# TSL2561_5V_REV-A.net
KiCad netlist of a schematic drawn in EAGLE
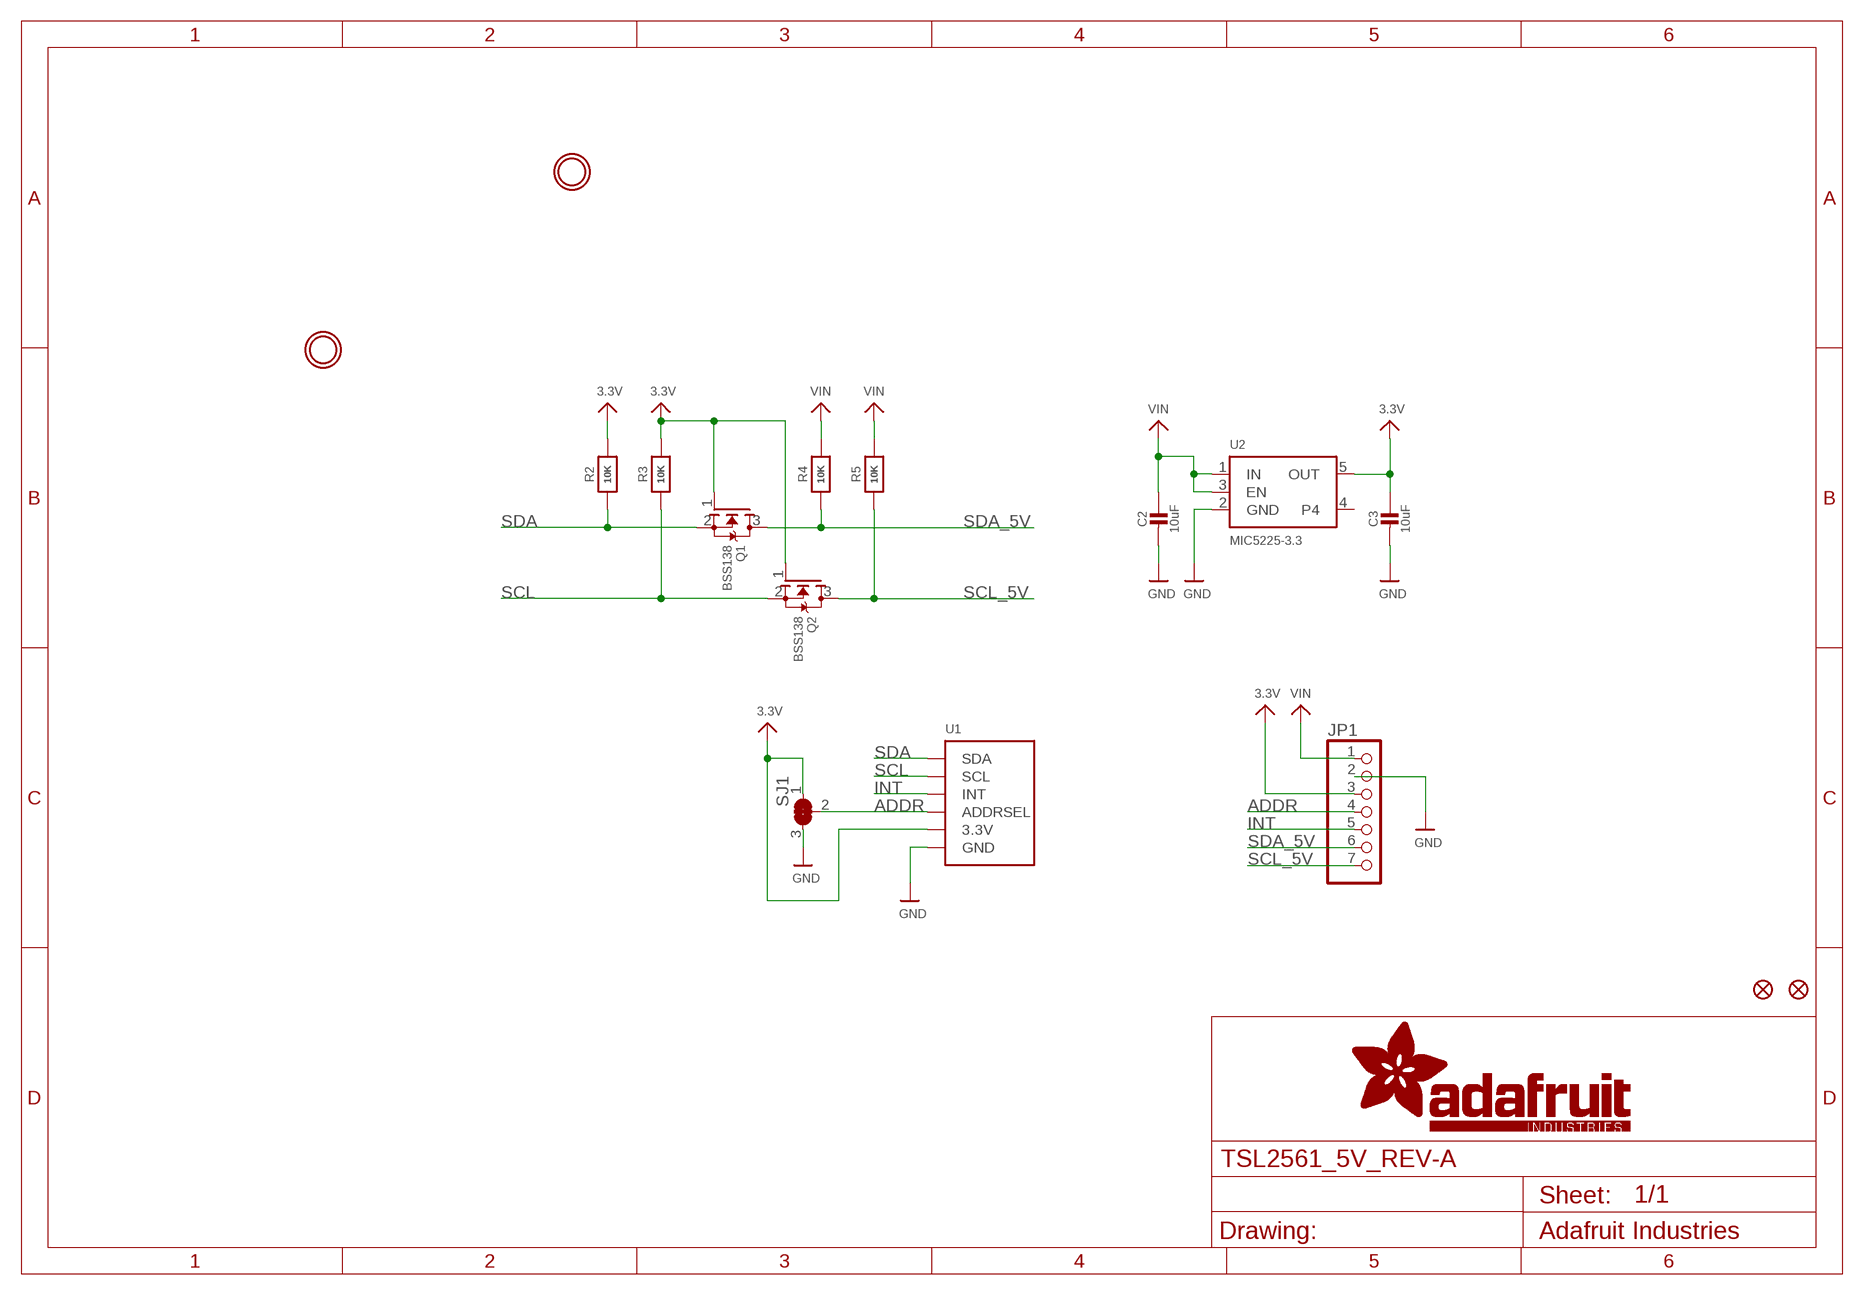
[diagram p0: schematic, sheet 1]

(export (version "E")
  (design (tool "Eeschema 10.0.6"))
  (components
    (comp (ref "C2")
      (value "10uF")
      (footprint "eagle-import:0805-NO")
      (libsource (lib "eagle-import") (part "CAP_CERAMIC0805-NOOUTLINE"))
    )
    (comp (ref "C3")
      (value "10uF")
      (footprint "eagle-import:0805-NO")
      (libsource (lib "eagle-import") (part "CAP_CERAMIC0805-NOOUTLINE"))
    )
    (comp (ref "FID1")
      (value "FIDUCIAL\"\"")
      (footprint "eagle-import:FIDUCIAL_1MM")
      (libsource (lib "eagle-import") (part "FIDUCIAL{dblquote}{dblquote}"))
    )
    (comp (ref "FID2")
      (value "FIDUCIAL\"\"")
      (footprint "eagle-import:FIDUCIAL_1MM")
      (libsource (lib "eagle-import") (part "FIDUCIAL{dblquote}{dblquote}"))
    )
    (comp (ref "JP1")
      (value "HEADER-1X7THICKER")
      (footprint "eagle-import:1X07_ROUND_76")
      (libsource (lib "eagle-import") (part "HEADER-1X7THICKER"))
    )
    (comp (ref "Q1")
      (value "BSS138")
      (footprint "eagle-import:SOT23-WIDE")
      (libsource (lib "eagle-import") (part "MOSFET-NWIDE"))
    )
    (comp (ref "Q2")
      (value "BSS138")
      (footprint "eagle-import:SOT23-WIDE")
      (libsource (lib "eagle-import") (part "MOSFET-NWIDE"))
    )
    (comp (ref "R2")
      (value "10K")
      (footprint "eagle-import:0805-NO")
      (libsource (lib "eagle-import") (part "RESISTOR0805_NOOUTLINE"))
    )
    (comp (ref "R3")
      (value "10K")
      (footprint "eagle-import:0805-NO")
      (libsource (lib "eagle-import") (part "RESISTOR0805_NOOUTLINE"))
    )
    (comp (ref "R4")
      (value "10K")
      (footprint "eagle-import:0805-NO")
      (libsource (lib "eagle-import") (part "RESISTOR0805_NOOUTLINE"))
    )
    (comp (ref "R5")
      (value "10K")
      (footprint "eagle-import:0805-NO")
      (libsource (lib "eagle-import") (part "RESISTOR0805_NOOUTLINE"))
    )
    (comp (ref "SJ1")
      (value "SOLDERJUMPER_2WAY")
      (footprint "eagle-import:SOLDERJUMPER_2WAY_OPEN_NOPASTE")
      (libsource (lib "eagle-import") (part "SOLDERJUMPER_2WAY"))
    )
    (comp (ref "U$18")
      (value "MOUNTINGHOLE2.5")
      (footprint "eagle-import:MOUNTINGHOLE_2.5_PLATED")
      (libsource (lib "eagle-import") (part "MOUNTINGHOLE2.5"))
    )
    (comp (ref "U$19")
      (value "MOUNTINGHOLE2.5")
      (footprint "eagle-import:MOUNTINGHOLE_2.5_PLATED")
      (libsource (lib "eagle-import") (part "MOUNTINGHOLE2.5"))
    )
    (comp (ref "U1")
      (value "LIGHT_TSL2561")
      (footprint "eagle-import:TSL2561_FN")
      (libsource (lib "eagle-import") (part "LIGHT_TSL2561"))
    )
    (comp (ref "U2")
      (value "MIC5225-3.3")
      (footprint "eagle-import:SOT23-5")
      (libsource (lib "eagle-import") (part "VREG_SOT23-5"))
    )
  )
  (nets
    (net (code "1") (name "/ADDR") (class "Default")
      (node (ref "JP1") (pin "4") (pinfunction "4_4") (pintype "passive"))
      (node (ref "SJ1") (pin "2") (pinfunction "2_2") (pintype "passive"))
      (node (ref "U1") (pin "ADR") (pinfunction "ADDRSEL_ADR") (pintype "bidirectional"))
    )
    (net (code "2") (name "/INT") (class "Default")
      (node (ref "JP1") (pin "5") (pinfunction "5_5") (pintype "passive"))
      (node (ref "U1") (pin "INT") (pinfunction "INT_INT") (pintype "bidirectional"))
    )
    (net (code "3") (name "/SCL") (class "Default")
      (node (ref "Q2") (pin "2") (pinfunction "S_2") (pintype "bidirectional"))
      (node (ref "R3") (pin "1") (pinfunction "1_1") (pintype "passive"))
      (node (ref "U1") (pin "CLK") (pinfunction "SCL_CLK") (pintype "bidirectional"))
    )
    (net (code "4") (name "/SCL_5V") (class "Default")
      (node (ref "JP1") (pin "7") (pinfunction "7_7") (pintype "passive"))
      (node (ref "Q2") (pin "3") (pinfunction "D_3") (pintype "bidirectional"))
      (node (ref "R5") (pin "1") (pinfunction "1_1") (pintype "passive"))
    )
    (net (code "5") (name "/SDA") (class "Default")
      (node (ref "Q1") (pin "2") (pinfunction "S_2") (pintype "bidirectional"))
      (node (ref "R2") (pin "1") (pinfunction "1_1") (pintype "passive"))
      (node (ref "U1") (pin "DATA") (pinfunction "SDA_DATA") (pintype "bidirectional"))
    )
    (net (code "6") (name "/SDA_5V") (class "Default")
      (node (ref "JP1") (pin "6") (pinfunction "6_6") (pintype "passive"))
      (node (ref "Q1") (pin "3") (pinfunction "D_3") (pintype "bidirectional"))
      (node (ref "R4") (pin "1") (pinfunction "1_1") (pintype "passive"))
    )
    (net (code "7") (name "3.3V") (class "Default")
      (node (ref "C3") (pin "1") (pinfunction "1_1") (pintype "passive"))
      (node (ref "JP1") (pin "3") (pinfunction "3_3") (pintype "passive"))
      (node (ref "Q1") (pin "1") (pinfunction "G_1") (pintype "bidirectional"))
      (node (ref "Q2") (pin "1") (pinfunction "G_1") (pintype "bidirectional"))
      (node (ref "R2") (pin "2") (pinfunction "2_2") (pintype "passive"))
      (node (ref "R3") (pin "2") (pinfunction "2_2") (pintype "passive"))
      (node (ref "SJ1") (pin "1") (pinfunction "1_1") (pintype "passive"))
      (node (ref "U1") (pin "VDD") (pinfunction "3.3V_VDD") (pintype "bidirectional"))
      (node (ref "U2") (pin "5") (pinfunction "OUT_5") (pintype "power_in"))
    )
    (net (code "8") (name "GND") (class "Default")
      (node (ref "C2") (pin "2") (pinfunction "2_2") (pintype "passive"))
      (node (ref "C3") (pin "2") (pinfunction "2_2") (pintype "passive"))
      (node (ref "JP1") (pin "2") (pinfunction "2_2") (pintype "passive"))
      (node (ref "SJ1") (pin "3") (pinfunction "3_3") (pintype "passive"))
      (node (ref "U1") (pin "VSS") (pinfunction "GND_VSS") (pintype "bidirectional"))
      (node (ref "U2") (pin "2") (pinfunction "GND_2") (pintype "power_in"))
    )
    (net (code "9") (name "VIN") (class "Default")
      (node (ref "C2") (pin "1") (pinfunction "1_1") (pintype "passive"))
      (node (ref "JP1") (pin "1") (pinfunction "1_1") (pintype "passive"))
      (node (ref "R4") (pin "2") (pinfunction "2_2") (pintype "passive"))
      (node (ref "R5") (pin "2") (pinfunction "2_2") (pintype "passive"))
      (node (ref "U2") (pin "1") (pinfunction "IN_1") (pintype "power_in"))
      (node (ref "U2") (pin "3") (pinfunction "EN_3") (pintype "input"))
    )
    (net (code "10") (name "unconnected-(U2-P4-Pad4)") (class "Default")
      (node (ref "U2") (pin "4") (pinfunction "P4_4") (pintype "bidirectional"))
    )
  )
)
